# TouScruino-v3.net
KiCad netlist of a schematic drawn in EAGLE
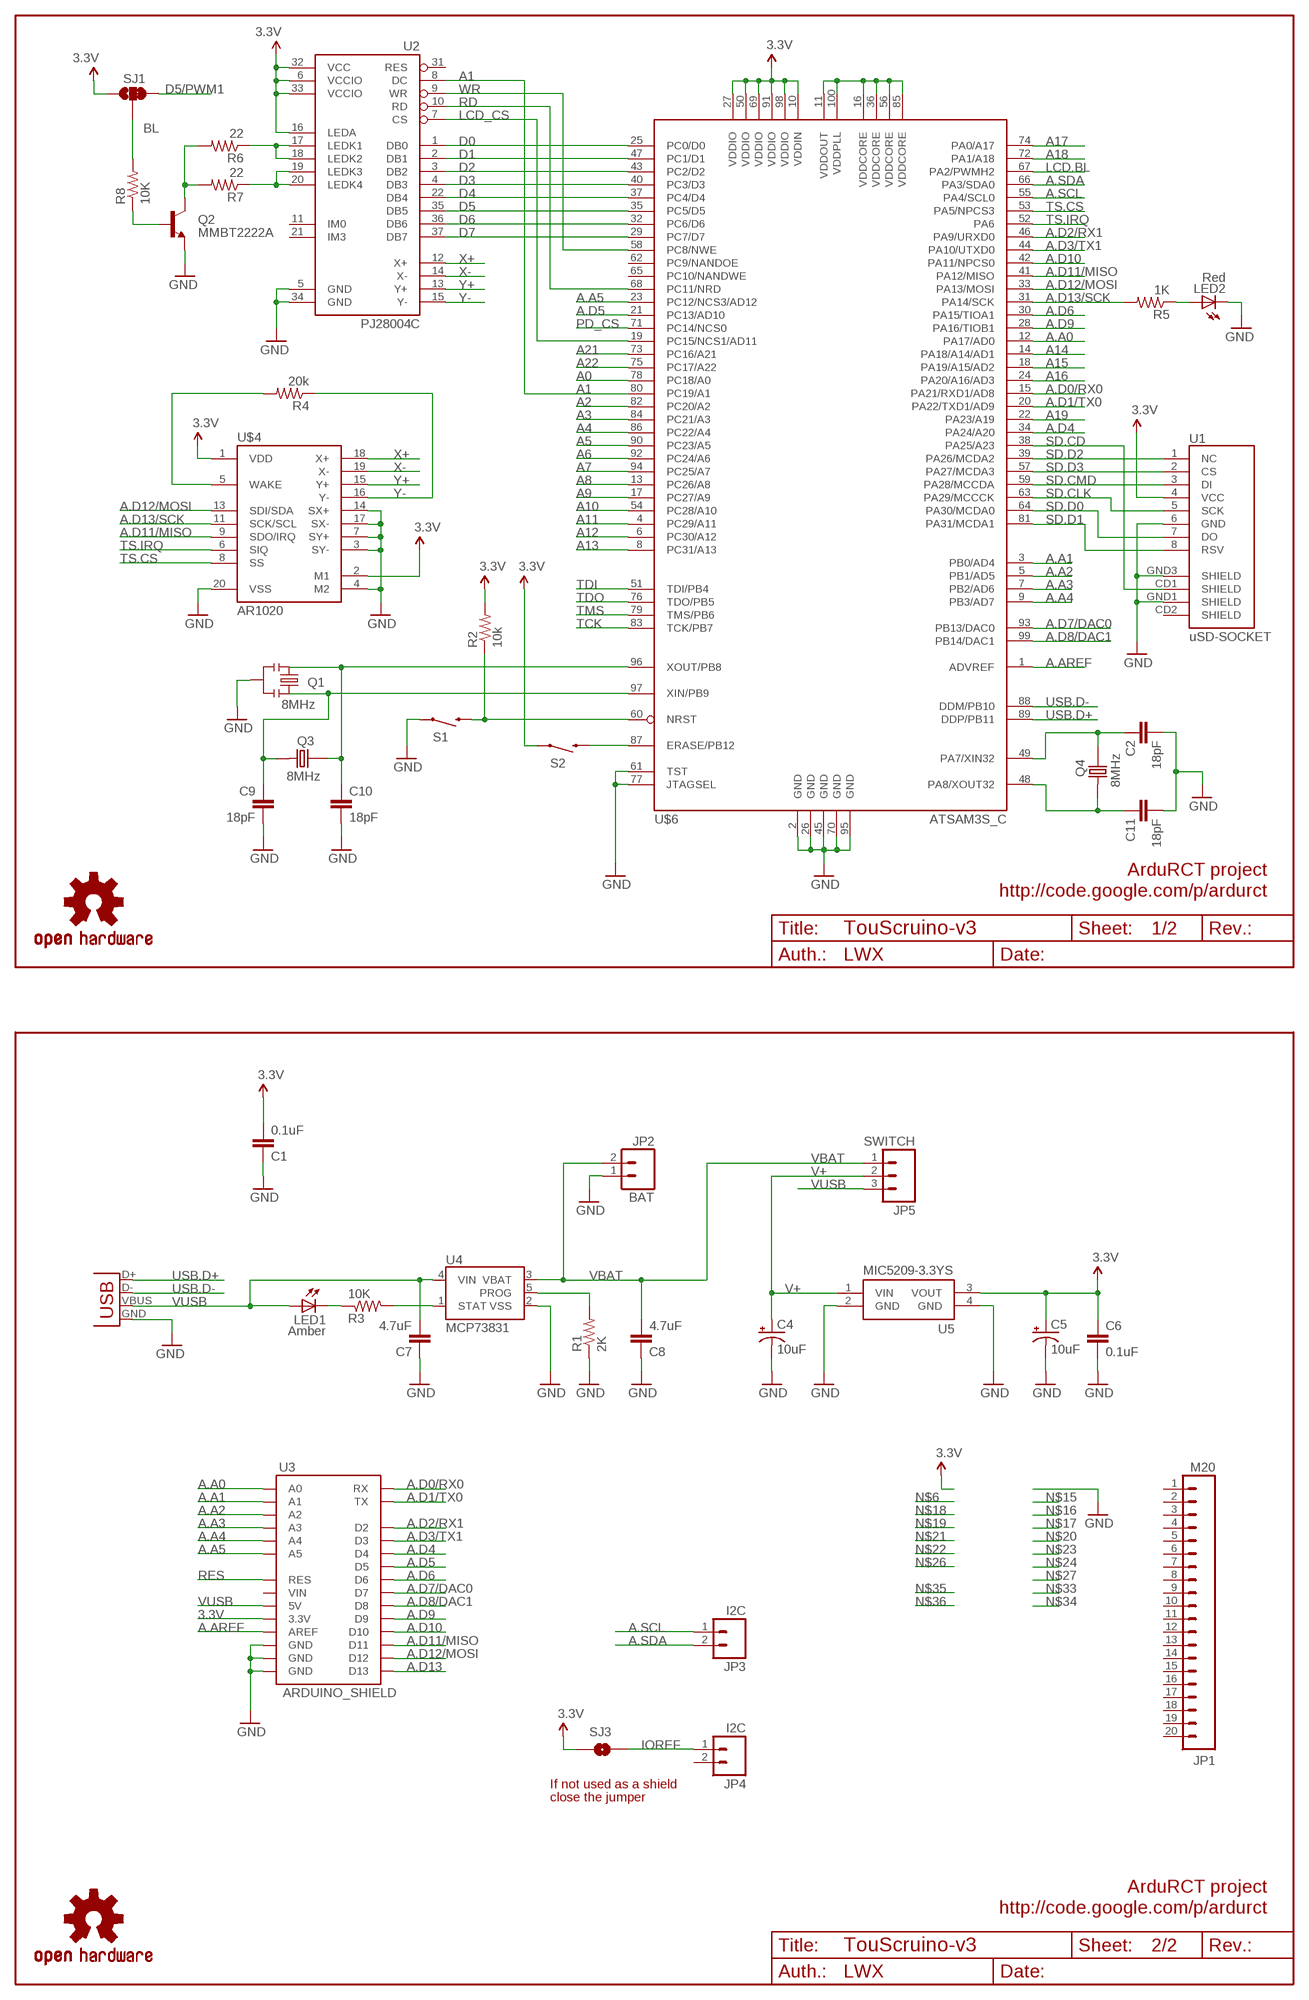
[diagram p0: schematic, sheet 1]

(export (version "E")
  (design (tool "Eeschema 10.0.6"))
  (components
    (comp (ref "C1")
      (value "0.1uF")
      (footprint "eagle-import:0805")
      (libsource (lib "eagle-import") (part "CAP0805"))
    )
    (comp (ref "C2")
      (value "18pF")
      (footprint "eagle-import:0603-CAP")
      (libsource (lib "eagle-import") (part "CAP0603-CAP"))
    )
    (comp (ref "C4")
      (value "10uF")
      (footprint "eagle-import:EIA3216")
      (libsource (lib "eagle-import") (part "CAP_POL1206"))
    )
    (comp (ref "C5")
      (value "10uF")
      (footprint "eagle-import:EIA3216")
      (libsource (lib "eagle-import") (part "CAP_POL1206"))
    )
    (comp (ref "C6")
      (value "0.1uF")
      (footprint "eagle-import:0805")
      (libsource (lib "eagle-import") (part "CAP0805"))
    )
    (comp (ref "C7")
      (value "4.7uF")
      (footprint "eagle-import:0805")
      (libsource (lib "eagle-import") (part "CAP0805"))
    )
    (comp (ref "C8")
      (value "4.7uF")
      (footprint "eagle-import:0805")
      (libsource (lib "eagle-import") (part "CAP0805"))
    )
    (comp (ref "C9")
      (value "18pF")
      (footprint "eagle-import:0603-CAP")
      (libsource (lib "eagle-import") (part "CAP0603-CAP"))
    )
    (comp (ref "C10")
      (value "18pF")
      (footprint "eagle-import:0603-CAP")
      (libsource (lib "eagle-import") (part "CAP0603-CAP"))
    )
    (comp (ref "C11")
      (value "18pF")
      (footprint "eagle-import:0603-CAP")
      (libsource (lib "eagle-import") (part "CAP0603-CAP"))
    )
    (comp (ref "JP1")
      (value "M20")
      (footprint "eagle-import:1X20")
      (libsource (lib "eagle-import") (part "M20"))
    )
    (comp (ref "JP2")
      (value "BAT")
      (footprint "eagle-import:JST-2-SMD")
      (libsource (lib "eagle-import") (part "M02-JST-2MM-SMT"))
    )
    (comp (ref "JP3")
      (value "I2C")
      (footprint "eagle-import:1X02")
      (libsource (lib "eagle-import") (part "M02"))
    )
    (comp (ref "JP4")
      (value "I2C")
      (footprint "eagle-import:1X02")
      (libsource (lib "eagle-import") (part "M02"))
    )
    (comp (ref "JP5")
      (value "SWITCH")
      (footprint "eagle-import:1X3_LONGPAD")
      (libsource (lib "eagle-import") (part "M03"))
    )
    (comp (ref "LED1")
      (value "Amber")
      (footprint "eagle-import:LED")
      (libsource (lib "eagle-import") (part "LED"))
    )
    (comp (ref "LED2")
      (value "Red")
      (footprint "eagle-import:LED-0805")
      (libsource (lib "eagle-import") (part "LED805"))
    )
    (comp (ref "Q1")
      (value "8MHz")
      (footprint "eagle-import:RESONATOR-SMD")
      (libsource (lib "eagle-import") (part "RESONATORSMD"))
    )
    (comp (ref "Q2")
      (value "MMBT2222A")
      (footprint "eagle-import:SOT23-3")
      (libsource (lib "eagle-import") (part "TRANSISTOR_NPNSOT23-3"))
    )
    (comp (ref "Q3")
      (value "8MHz")
      (footprint "eagle-import:CRYSTAL_5X3.2")
      (libsource (lib "eagle-import") (part "CRYSTAL_5X3.2"))
    )
    (comp (ref "Q4")
      (value "8MHz")
      (footprint "eagle-import:CRYSTAL_5X3.2")
      (libsource (lib "eagle-import") (part "CRYSTAL_5X3.2"))
    )
    (comp (ref "R1")
      (value "2K")
      (footprint "eagle-import:0805")
      (libsource (lib "eagle-import") (part "RESISTOR0805-RES"))
    )
    (comp (ref "R2")
      (value "10k")
      (footprint "eagle-import:0805")
      (libsource (lib "eagle-import") (part "RESISTOR0805-RES"))
    )
    (comp (ref "R3")
      (value "10K")
      (footprint "eagle-import:0805")
      (libsource (lib "eagle-import") (part "RESISTOR0805-RES"))
    )
    (comp (ref "R4")
      (value "20k")
      (footprint "eagle-import:0805")
      (libsource (lib "eagle-import") (part "RESISTOR0805-RES"))
    )
    (comp (ref "R5")
      (value "1K")
      (footprint "eagle-import:0805")
      (libsource (lib "eagle-import") (part "RESISTOR0805-RES"))
    )
    (comp (ref "R6")
      (value "22")
      (footprint "eagle-import:0805")
      (libsource (lib "eagle-import") (part "RESISTOR0805-RES"))
    )
    (comp (ref "R7")
      (value "22")
      (footprint "eagle-import:0805")
      (libsource (lib "eagle-import") (part "RESISTOR0805-RES"))
    )
    (comp (ref "R8")
      (value "10K")
      (footprint "eagle-import:0805")
      (libsource (lib "eagle-import") (part "RESISTOR0805-RES"))
    )
    (comp (ref "S1")
      (value "SWITCH-MOMENTARY-2SMD")
      (footprint "eagle-import:TACTILE_SWITCH_SMD")
      (libsource (lib "eagle-import") (part "SWITCH-MOMENTARY-2SMD"))
    )
    (comp (ref "S2")
      (value "SWITCH-MOMENTARY-2SMD")
      (footprint "eagle-import:TACTILE_SWITCH_SMD")
      (libsource (lib "eagle-import") (part "SWITCH-MOMENTARY-2SMD"))
    )
    (comp (ref "SJ1")
      (value "SJ_2WAYS_1-2")
      (footprint "eagle-import:SJ_2WAYS_1-2_S")
      (libsource (lib "eagle-import") (part "SJ_2WAYS_1-2"))
    )
    (comp (ref "SJ3")
      (value "SOLDERJUMPERNO")
      (footprint "eagle-import:SJ_2S-NO")
      (libsource (lib "eagle-import") (part "SOLDERJUMPERNO"))
    )
    (comp (ref "U$3")
      (value "OSHW-LOGOM")
      (footprint "eagle-import:OSHW-LOGO-M")
      (libsource (lib "eagle-import") (part "OSHW-LOGOM"))
    )
    (comp (ref "U$4")
      (value "AR1020")
      (footprint "eagle-import:SSOP20")
      (libsource (lib "eagle-import") (part "AR1020"))
    )
    (comp (ref "U$5")
      (value "OSHW-LOGOM")
      (footprint "eagle-import:OSHW-LOGO-M")
      (libsource (lib "eagle-import") (part "OSHW-LOGOM"))
    )
    (comp (ref "U$6")
      (value "ATSAM3S_C")
      (footprint "eagle-import:TQFP100")
      (libsource (lib "eagle-import") (part "ATSAM3S_C"))
    )
    (comp (ref "U1")
      (value "uSD-SOCKET")
      (footprint "eagle-import:MICRO-SD-SOCKET-PP")
      (libsource (lib "eagle-import") (part "USD-SOCKETNEW"))
    )
    (comp (ref "U2")
      (value "PJ28004C")
      (footprint "eagle-import:PJ28004C")
      (libsource (lib "eagle-import") (part "PJ28004C"))
    )
    (comp (ref "U3")
      (value "ARDUINO_SHIELD")
      (footprint "eagle-import:ARDUINO_SHIELD")
      (libsource (lib "eagle-import") (part "ARDUINO_SHIELD"))
    )
    (comp (ref "U4")
      (value "MCP73831")
      (footprint "eagle-import:SOT23-5")
      (libsource (lib "eagle-import") (part "MCP73831"))
    )
    (comp (ref "U5")
      (value "MIC5209-3.3YS")
      (footprint "eagle-import:SOT223")
      (libsource (lib "eagle-import") (part "MIC5209"))
    )
    (comp (ref "X1")
      (value "USBSMD")
      (footprint "eagle-import:USB-MINIB")
      (libsource (lib "eagle-import") (part "USBSMD"))
    )
  )
  (nets
    (net (code "1") (name "/A.A0") (class "Default")
      (node (ref "U$6") (pin "12") (pinfunction "PA17/AD0_12") (pintype "bidirectional"))
      (node (ref "U3") (pin "A0") (pinfunction "A0_A0") (pintype "bidirectional"))
    )
    (net (code "2") (name "/A.A1") (class "Default")
      (node (ref "U$6") (pin "3") (pinfunction "PB0/AD4_3") (pintype "bidirectional"))
      (node (ref "U3") (pin "A1") (pinfunction "A1_A1") (pintype "bidirectional"))
    )
    (net (code "3") (name "/A.A2") (class "Default")
      (node (ref "U$6") (pin "5") (pinfunction "PB1/AD5_5") (pintype "bidirectional"))
      (node (ref "U3") (pin "A2") (pinfunction "A2_A2") (pintype "bidirectional"))
    )
    (net (code "4") (name "/A.A3") (class "Default")
      (node (ref "U$6") (pin "7") (pinfunction "PB2/AD6_7") (pintype "bidirectional"))
      (node (ref "U3") (pin "A3") (pinfunction "A3_A3") (pintype "bidirectional"))
    )
    (net (code "5") (name "/A.A4") (class "Default")
      (node (ref "U$6") (pin "9") (pinfunction "PB3/AD7_9") (pintype "bidirectional"))
      (node (ref "U3") (pin "A4") (pinfunction "A4_A4") (pintype "bidirectional"))
    )
    (net (code "6") (name "/A.A5") (class "Default")
      (node (ref "U$6") (pin "23") (pinfunction "PC12/NCS3/AD12_23") (pintype "bidirectional"))
      (node (ref "U3") (pin "A5") (pinfunction "A5_A5") (pintype "bidirectional"))
    )
    (net (code "7") (name "/A.AREF") (class "Default")
      (node (ref "U$6") (pin "1") (pinfunction "ADVREF_1") (pintype "bidirectional"))
      (node (ref "U3") (pin "AREF") (pinfunction "AREF_AREF") (pintype "bidirectional"))
    )
    (net (code "8") (name "/A.D0{slash}RX0") (class "Default")
      (node (ref "U$6") (pin "15") (pinfunction "PA21/RXD1/AD8_15") (pintype "bidirectional"))
      (node (ref "U3") (pin "RX") (pinfunction "RX_RX") (pintype "bidirectional"))
    )
    (net (code "9") (name "/A.D1{slash}TX0") (class "Default")
      (node (ref "U$6") (pin "20") (pinfunction "PA22/TXD1/AD9_20") (pintype "bidirectional"))
      (node (ref "U3") (pin "TX") (pinfunction "TX_TX") (pintype "bidirectional"))
    )
    (net (code "10") (name "/A.D2{slash}RX1") (class "Default")
      (node (ref "U$6") (pin "46") (pinfunction "PA9/URXD0_46") (pintype "bidirectional"))
      (node (ref "U3") (pin "D2") (pinfunction "D2_D2") (pintype "bidirectional"))
    )
    (net (code "11") (name "/A.D3{slash}TX1") (class "Default")
      (node (ref "U$6") (pin "44") (pinfunction "PA10/UTXD0_44") (pintype "bidirectional"))
      (node (ref "U3") (pin "D3") (pinfunction "D3_D3") (pintype "bidirectional"))
    )
    (net (code "12") (name "/A.D4") (class "Default")
      (node (ref "U$6") (pin "34") (pinfunction "PA24/A20_34") (pintype "bidirectional"))
      (node (ref "U3") (pin "D4") (pinfunction "D4_D4") (pintype "bidirectional"))
    )
    (net (code "13") (name "/A.D5") (class "Default")
      (node (ref "U$6") (pin "21") (pinfunction "PC13/AD10_21") (pintype "bidirectional"))
      (node (ref "U3") (pin "D5") (pinfunction "D5_D5") (pintype "bidirectional"))
    )
    (net (code "14") (name "/A.D6") (class "Default")
      (node (ref "U$6") (pin "30") (pinfunction "PA15/TIOA1_30") (pintype "bidirectional"))
      (node (ref "U3") (pin "D6") (pinfunction "D6_D6") (pintype "bidirectional"))
    )
    (net (code "15") (name "/A.D7{slash}DAC0") (class "Default")
      (node (ref "U$6") (pin "93") (pinfunction "PB13/DAC0_93") (pintype "bidirectional"))
      (node (ref "U3") (pin "D7") (pinfunction "D7_D7") (pintype "bidirectional"))
    )
    (net (code "16") (name "/A.D8{slash}DAC1") (class "Default")
      (node (ref "U$6") (pin "99") (pinfunction "PB14/DAC1_99") (pintype "bidirectional"))
      (node (ref "U3") (pin "D8") (pinfunction "D8_D8") (pintype "bidirectional"))
    )
    (net (code "17") (name "/A.D9") (class "Default")
      (node (ref "U$6") (pin "28") (pinfunction "PA16/TIOB1_28") (pintype "bidirectional"))
      (node (ref "U3") (pin "D9") (pinfunction "D9_D9") (pintype "bidirectional"))
    )
    (net (code "18") (name "/A.D10") (class "Default")
      (node (ref "U$6") (pin "42") (pinfunction "PA11/NPCS0_42") (pintype "bidirectional"))
      (node (ref "U3") (pin "D10") (pinfunction "D10_D10") (pintype "bidirectional"))
    )
    (net (code "19") (name "/A.D11{slash}MISO") (class "Default")
      (node (ref "U$4") (pin "9") (pinfunction "SDO/IRQ_9") (pintype "bidirectional"))
      (node (ref "U$6") (pin "41") (pinfunction "PA12/MISO_41") (pintype "bidirectional"))
      (node (ref "U3") (pin "D11") (pinfunction "D11_D11") (pintype "bidirectional"))
    )
    (net (code "20") (name "/A.D12{slash}MOSI") (class "Default")
      (node (ref "U$4") (pin "13") (pinfunction "SDI/SDA_13") (pintype "bidirectional"))
      (node (ref "U$6") (pin "33") (pinfunction "PA13/MOSI_33") (pintype "bidirectional"))
      (node (ref "U3") (pin "D12") (pinfunction "D12_D12") (pintype "bidirectional"))
    )
    (net (code "21") (name "/A.D13") (class "Default")
      (node (ref "U3") (pin "D13") (pinfunction "D13_D13") (pintype "bidirectional"))
    )
    (net (code "22") (name "/A.D13{slash}SCK") (class "Default")
      (node (ref "R5") (pin "2") (pinfunction "2_2") (pintype "passive"))
      (node (ref "U$4") (pin "11") (pinfunction "SCK/SCL_11") (pintype "bidirectional"))
      (node (ref "U$6") (pin "31") (pinfunction "PA14/SCK_31") (pintype "bidirectional"))
    )
    (net (code "23") (name "/A.SCL") (class "Default")
      (node (ref "JP3") (pin "1") (pinfunction "1_1") (pintype "passive"))
      (node (ref "U$6") (pin "55") (pinfunction "PA4/SCL0_55") (pintype "bidirectional"))
    )
    (net (code "24") (name "/A.SDA") (class "Default")
      (node (ref "JP3") (pin "2") (pinfunction "2_2") (pintype "passive"))
      (node (ref "U$6") (pin "66") (pinfunction "PA3/SDA0_66") (pintype "bidirectional"))
    )
    (net (code "25") (name "/A0") (class "Default")
      (node (ref "U$6") (pin "78") (pinfunction "PC18/A0_78") (pintype "bidirectional"))
    )
    (net (code "26") (name "/A1") (class "Default")
      (node (ref "U$6") (pin "80") (pinfunction "PC19/A1_80") (pintype "bidirectional"))
      (node (ref "U2") (pin "8") (pinfunction "DC_8") (pintype "bidirectional"))
    )
    (net (code "27") (name "/A2") (class "Default")
      (node (ref "U$6") (pin "82") (pinfunction "PC20/A2_82") (pintype "bidirectional"))
    )
    (net (code "28") (name "/A3") (class "Default")
      (node (ref "U$6") (pin "84") (pinfunction "PC21/A3_84") (pintype "bidirectional"))
    )
    (net (code "29") (name "/A4") (class "Default")
      (node (ref "U$6") (pin "86") (pinfunction "PC22/A4_86") (pintype "bidirectional"))
    )
    (net (code "30") (name "/A5") (class "Default")
      (node (ref "U$6") (pin "90") (pinfunction "PC23/A5_90") (pintype "bidirectional"))
    )
    (net (code "31") (name "/A6") (class "Default")
      (node (ref "U$6") (pin "92") (pinfunction "PC24/A6_92") (pintype "bidirectional"))
    )
    (net (code "32") (name "/A7") (class "Default")
      (node (ref "U$6") (pin "94") (pinfunction "PC25/A7_94") (pintype "bidirectional"))
    )
    (net (code "33") (name "/A8") (class "Default")
      (node (ref "U$6") (pin "13") (pinfunction "PC26/A8_13") (pintype "bidirectional"))
    )
    (net (code "34") (name "/A9") (class "Default")
      (node (ref "U$6") (pin "17") (pinfunction "PC27/A9_17") (pintype "bidirectional"))
    )
    (net (code "35") (name "/A10") (class "Default")
      (node (ref "U$6") (pin "54") (pinfunction "PC28/A10_54") (pintype "bidirectional"))
    )
    (net (code "36") (name "/A11") (class "Default")
      (node (ref "U$6") (pin "4") (pinfunction "PC29/A11_4") (pintype "bidirectional"))
    )
    (net (code "37") (name "/A12") (class "Default")
      (node (ref "U$6") (pin "6") (pinfunction "PC30/A12_6") (pintype "bidirectional"))
    )
    (net (code "38") (name "/A13") (class "Default")
      (node (ref "U$6") (pin "8") (pinfunction "PC31/A13_8") (pintype "bidirectional"))
    )
    (net (code "39") (name "/A14") (class "Default")
      (node (ref "U$6") (pin "14") (pinfunction "PA18/A14/AD1_14") (pintype "bidirectional"))
    )
    (net (code "40") (name "/A15") (class "Default")
      (node (ref "U$6") (pin "18") (pinfunction "PA19/A15/AD2_18") (pintype "bidirectional"))
    )
    (net (code "41") (name "/A16") (class "Default")
      (node (ref "U$6") (pin "24") (pinfunction "PA20/A16/AD3_24") (pintype "bidirectional"))
    )
    (net (code "42") (name "/A17") (class "Default")
      (node (ref "U$6") (pin "74") (pinfunction "PA0/A17_74") (pintype "bidirectional"))
    )
    (net (code "43") (name "/A18") (class "Default")
      (node (ref "U$6") (pin "72") (pinfunction "PA1/A18_72") (pintype "bidirectional"))
    )
    (net (code "44") (name "/A19") (class "Default")
      (node (ref "U$6") (pin "22") (pinfunction "PA23/A19_22") (pintype "bidirectional"))
    )
    (net (code "45") (name "/A21") (class "Default")
      (node (ref "U$6") (pin "73") (pinfunction "PC16/A21_73") (pintype "bidirectional"))
    )
    (net (code "46") (name "/A22") (class "Default")
      (node (ref "U$6") (pin "75") (pinfunction "PC17/A22_75") (pintype "bidirectional"))
    )
    (net (code "47") (name "/BL") (class "Default")
      (node (ref "R8") (pin "2") (pinfunction "2_2") (pintype "passive"))
      (node (ref "SJ1") (pin "2") (pinfunction "2_2") (pintype "passive"))
    )
    (net (code "48") (name "/D0") (class "Default")
      (node (ref "U$6") (pin "25") (pinfunction "PC0/D0_25") (pintype "bidirectional"))
      (node (ref "U2") (pin "1") (pinfunction "DB0_1") (pintype "bidirectional"))
    )
    (net (code "49") (name "/D1") (class "Default")
      (node (ref "U$6") (pin "47") (pinfunction "PC1/D1_47") (pintype "bidirectional"))
      (node (ref "U2") (pin "2") (pinfunction "DB1_2") (pintype "bidirectional"))
    )
    (net (code "50") (name "/D2") (class "Default")
      (node (ref "U$6") (pin "43") (pinfunction "PC2/D2_43") (pintype "bidirectional"))
      (node (ref "U2") (pin "3") (pinfunction "DB2_3") (pintype "bidirectional"))
    )
    (net (code "51") (name "/D3") (class "Default")
      (node (ref "U$6") (pin "40") (pinfunction "PC3/D3_40") (pintype "bidirectional"))
      (node (ref "U2") (pin "4") (pinfunction "DB3_4") (pintype "bidirectional"))
    )
    (net (code "52") (name "/D4") (class "Default")
      (node (ref "U$6") (pin "37") (pinfunction "PC4/D4_37") (pintype "bidirectional"))
      (node (ref "U2") (pin "22") (pinfunction "DB4_22") (pintype "bidirectional"))
    )
    (net (code "53") (name "/D5") (class "Default")
      (node (ref "U$6") (pin "35") (pinfunction "PC5/D5_35") (pintype "bidirectional"))
      (node (ref "U2") (pin "35") (pinfunction "DB5_35") (pintype "bidirectional"))
    )
    (net (code "54") (name "/D5{slash}PWM1") (class "Default")
      (node (ref "SJ1") (pin "1") (pinfunction "1_1") (pintype "passive"))
    )
    (net (code "55") (name "/D6") (class "Default")
      (node (ref "U$6") (pin "32") (pinfunction "PC6/D6_32") (pintype "bidirectional"))
      (node (ref "U2") (pin "36") (pinfunction "DB6_36") (pintype "bidirectional"))
    )
    (net (code "56") (name "/D7") (class "Default")
      (node (ref "U$6") (pin "29") (pinfunction "PC7/D7_29") (pintype "bidirectional"))
      (node (ref "U2") (pin "37") (pinfunction "DB7_37") (pintype "bidirectional"))
    )
    (net (code "57") (name "/IOREF") (class "Default")
      (node (ref "JP4") (pin "1") (pinfunction "1_1") (pintype "passive"))
      (node (ref "SJ3") (pin "2") (pinfunction "2_2") (pintype "passive"))
    )
    (net (code "58") (name "/LCD.BL") (class "Default")
      (node (ref "U$6") (pin "67") (pinfunction "PA2/PWMH2_67") (pintype "bidirectional"))
    )
    (net (code "59") (name "/LCD_CS") (class "Default")
      (node (ref "U$6") (pin "19") (pinfunction "PC15/NCS1/AD11_19") (pintype "bidirectional"))
      (node (ref "U2") (pin "7") (pinfunction "CS_7") (pintype "bidirectional"))
    )
    (net (code "77") (name "/PD_CS") (class "Default")
      (node (ref "U$6") (pin "71") (pinfunction "PC14/NCS0_71") (pintype "bidirectional"))
    )
    (net (code "78") (name "/RD") (class "Default")
      (node (ref "U$6") (pin "68") (pinfunction "PC11/NRD_68") (pintype "bidirectional"))
      (node (ref "U2") (pin "10") (pinfunction "RD_10") (pintype "bidirectional"))
    )
    (net (code "79") (name "/RES") (class "Default")
      (node (ref "U3") (pin "RES") (pinfunction "RES_RES") (pintype "bidirectional"))
    )
    (net (code "80") (name "/SD.CD") (class "Default")
      (node (ref "U$6") (pin "38") (pinfunction "PA25/A23_38") (pintype "bidirectional"))
      (node (ref "U1") (pin "CD1") (pinfunction "SHIELD_CD1") (pintype "bidirectional"))
    )
    (net (code "81") (name "/SD.CLK") (class "Default")
      (node (ref "U$6") (pin "63") (pinfunction "PA29/MCCCK_63") (pintype "bidirectional"))
      (node (ref "U1") (pin "5") (pinfunction "SCK_5") (pintype "bidirectional"))
    )
    (net (code "82") (name "/SD.CMD") (class "Default")
      (node (ref "U$6") (pin "59") (pinfunction "PA28/MCCDA_59") (pintype "bidirectional"))
      (node (ref "U1") (pin "3") (pinfunction "DI_3") (pintype "bidirectional"))
    )
    (net (code "83") (name "/SD.D0") (class "Default")
      (node (ref "U$6") (pin "64") (pinfunction "PA30/MCDA0_64") (pintype "bidirectional"))
      (node (ref "U1") (pin "7") (pinfunction "DO_7") (pintype "bidirectional"))
    )
    (net (code "84") (name "/SD.D1") (class "Default")
      (node (ref "U$6") (pin "81") (pinfunction "PA31/MCDA1_81") (pintype "bidirectional"))
      (node (ref "U1") (pin "8") (pinfunction "RSV_8") (pintype "bidirectional"))
    )
    (net (code "85") (name "/SD.D2") (class "Default")
      (node (ref "U$6") (pin "39") (pinfunction "PA26/MCDA2_39") (pintype "bidirectional"))
      (node (ref "U1") (pin "1") (pinfunction "NC_1") (pintype "bidirectional"))
    )
    (net (code "86") (name "/SD.D3") (class "Default")
      (node (ref "U$6") (pin "57") (pinfunction "PA27/MCDA3_57") (pintype "bidirectional"))
      (node (ref "U1") (pin "2") (pinfunction "CS_2") (pintype "bidirectional"))
    )
    (net (code "87") (name "/TCK") (class "Default")
      (node (ref "U$6") (pin "83") (pinfunction "TCK/PB7_83") (pintype "bidirectional"))
    )
    (net (code "88") (name "/TDI") (class "Default")
      (node (ref "U$6") (pin "51") (pinfunction "TDI/PB4_51") (pintype "bidirectional"))
    )
    (net (code "89") (name "/TDO") (class "Default")
      (node (ref "U$6") (pin "76") (pinfunction "TDO/PB5_76") (pintype "bidirectional"))
    )
    (net (code "90") (name "/TMS") (class "Default")
      (node (ref "U$6") (pin "79") (pinfunction "TMS/PB6_79") (pintype "bidirectional"))
    )
    (net (code "91") (name "/TS.CS") (class "Default")
      (node (ref "U$4") (pin "8") (pinfunction "SS_8") (pintype "bidirectional"))
      (node (ref "U$6") (pin "53") (pinfunction "PA5/NPCS3_53") (pintype "bidirectional"))
    )
    (net (code "92") (name "/TS.IRQ") (class "Default")
      (node (ref "U$4") (pin "6") (pinfunction "SIQ_6") (pintype "bidirectional"))
      (node (ref "U$6") (pin "52") (pinfunction "PA6_52") (pintype "bidirectional"))
    )
    (net (code "93") (name "/USB.D+") (class "Default")
      (node (ref "U$6") (pin "89") (pinfunction "DDP/PB11_89") (pintype "bidirectional"))
      (node (ref "X1") (pin "D+") (pinfunction "D+_D+") (pintype "bidirectional"))
    )
    (net (code "94") (name "/USB.D-") (class "Default")
      (node (ref "U$6") (pin "88") (pinfunction "DDM/PB10_88") (pintype "bidirectional"))
      (node (ref "X1") (pin "D-") (pinfunction "D-_D-") (pintype "bidirectional"))
    )
    (net (code "95") (name "/V+") (class "Default")
      (node (ref "C4") (pin "A") (pinfunction "+_A") (pintype "passive"))
      (node (ref "JP5") (pin "2") (pinfunction "2_2") (pintype "passive"))
      (node (ref "U5") (pin "1") (pinfunction "VIN_1") (pintype "bidirectional"))
    )
    (net (code "96") (name "/VBAT") (class "Default")
      (node (ref "C8") (pin "2") (pinfunction "2_2") (pintype "passive"))
      (node (ref "JP2") (pin "2") (pinfunction "2_2") (pintype "passive"))
      (node (ref "JP5") (pin "1") (pinfunction "1_1") (pintype "passive"))
      (node (ref "U4") (pin "3") (pinfunction "VBAT_3") (pintype "power_in"))
    )
    (net (code "97") (name "/VUSB") (class "Default")
      (node (ref "C7") (pin "2") (pinfunction "2_2") (pintype "passive"))
      (node (ref "JP5") (pin "3") (pinfunction "3_3") (pintype "passive"))
      (node (ref "LED1") (pin "A1") (pinfunction "A_A1") (pintype "passive"))
      (node (ref "U3") (pin "5V") (pinfunction "5V_5V") (pintype "bidirectional"))
      (node (ref "U4") (pin "4") (pinfunction "VIN_4") (pintype "power_in"))
      (node (ref "X1") (pin "VBUS") (pinfunction "VBUS_VBUS") (pintype "bidirectional"))
    )
    (net (code "98") (name "/WR") (class "Default")
      (node (ref "U$6") (pin "58") (pinfunction "PC8/NWE_58") (pintype "bidirectional"))
      (node (ref "U2") (pin "9") (pinfunction "WR_9") (pintype "bidirectional"))
    )
    (net (code "99") (name "/X+") (class "Default")
      (node (ref "U$4") (pin "18") (pinfunction "X+_18") (pintype "bidirectional"))
      (node (ref "U2") (pin "12") (pinfunction "X+_12") (pintype "bidirectional"))
    )
    (net (code "100") (name "/X-") (class "Default")
      (node (ref "U$4") (pin "19") (pinfunction "X-_19") (pintype "bidirectional"))
      (node (ref "U2") (pin "14") (pinfunction "X-_14") (pintype "bidirectional"))
    )
    (net (code "101") (name "/Y+") (class "Default")
      (node (ref "U$4") (pin "15") (pinfunction "Y+_15") (pintype "bidirectional"))
      (node (ref "U2") (pin "13") (pinfunction "Y+_13") (pintype "bidirectional"))
    )
    (net (code "102") (name "/Y-") (class "Default")
      (node (ref "R4") (pin "1") (pinfunction "1_1") (pintype "passive"))
      (node (ref "U$4") (pin "16") (pinfunction "Y-_16") (pintype "bidirectional"))
      (node (ref "U2") (pin "15") (pinfunction "Y-_15") (pintype "bidirectional"))
    )
    (net (code "103") (name "3.3V") (class "Default")
      (node (ref "C1") (pin "2") (pinfunction "2_2") (pintype "passive"))
      (node (ref "C5") (pin "A") (pinfunction "+_A") (pintype "passive"))
      (node (ref "C6") (pin "1") (pinfunction "1_1") (pintype "passive"))
      (node (ref "R2") (pin "2") (pinfunction "2_2") (pintype "passive"))
      (node (ref "S2") (pin "1") (pinfunction "1_1") (pintype "passive"))
      (node (ref "SJ1") (pin "3") (pinfunction "3_3") (pintype "passive"))
      (node (ref "SJ3") (pin "1") (pinfunction "1_1") (pintype "passive"))
      (node (ref "U$4") (pin "1") (pinfunction "VDD_1") (pintype "bidirectional"))
      (node (ref "U$4") (pin "2") (pinfunction "M1_2") (pintype "bidirectional"))
      (node (ref "U$6") (pin "10") (pinfunction "VDDIN_10") (pintype "bidirectional"))
      (node (ref "U$6") (pin "27") (pinfunction "VDDIO_27") (pintype "bidirectional"))
      (node (ref "U$6") (pin "50") (pinfunction "VDDIO_50") (pintype "bidirectional"))
      (node (ref "U$6") (pin "69") (pinfunction "VDDIO_69") (pintype "bidirectional"))
      (node (ref "U$6") (pin "91") (pinfunction "VDDIO_91") (pintype "bidirectional"))
      (node (ref "U$6") (pin "98") (pinfunction "VDDIO_98") (pintype "bidirectional"))
      (node (ref "U1") (pin "4") (pinfunction "VCC_4") (pintype "bidirectional"))
      (node (ref "U2") (pin "16") (pinfunction "LEDA_16") (pintype "bidirectional"))
      (node (ref "U2") (pin "32") (pinfunction "VCC_32") (pintype "bidirectional"))
      (node (ref "U2") (pin "33") (pinfunction "VCCIO_33") (pintype "bidirectional"))
      (node (ref "U2") (pin "6") (pinfunction "VCCIO_6") (pintype "bidirectional"))
      (node (ref "U3") (pin "3.3V") (pinfunction "3.3V_3.3V") (pintype "bidirectional"))
      (node (ref "U5") (pin "3") (pinfunction "VOUT_3") (pintype "bidirectional"))
    )
    (net (code "104") (name "GND") (class "Default")
      (node (ref "C1") (pin "1") (pinfunction "1_1") (pintype "passive"))
      (node (ref "C10") (pin "2") (pinfunction "2_2") (pintype "passive"))
      (node (ref "C11") (pin "2") (pinfunction "2_2") (pintype "passive"))
      (node (ref "C2") (pin "2") (pinfunction "2_2") (pintype "passive"))
      (node (ref "C4") (pin "C") (pinfunction "-_C") (pintype "passive"))
      (node (ref "C5") (pin "C") (pinfunction "-_C") (pintype "passive"))
      (node (ref "C6") (pin "2") (pinfunction "2_2") (pintype "passive"))
      (node (ref "C7") (pin "1") (pinfunction "1_1") (pintype "passive"))
      (node (ref "C8") (pin "1") (pinfunction "1_1") (pintype "passive"))
      (node (ref "C9") (pin "2") (pinfunction "2_2") (pintype "passive"))
      (node (ref "JP2") (pin "1") (pinfunction "1_1") (pintype "passive"))
      (node (ref "LED2") (pin "2") (pinfunction "C_2") (pintype "passive"))
      (node (ref "Q1") (pin "2") (pinfunction "2_2") (pintype "passive"))
      (node (ref "Q2") (pin "2") (pinfunction "E_2") (pintype "passive"))
      (node (ref "R1") (pin "1") (pinfunction "1_1") (pintype "passive"))
      (node (ref "S1") (pin "1") (pinfunction "1_1") (pintype "passive"))
      (node (ref "U$4") (pin "14") (pinfunction "SX+_14") (pintype "bidirectional"))
      (node (ref "U$4") (pin "17") (pinfunction "SX-_17") (pintype "bidirectional"))
      (node (ref "U$4") (pin "20") (pinfunction "VSS_20") (pintype "bidirectional"))
      (node (ref "U$4") (pin "3") (pinfunction "SY-_3") (pintype "bidirectional"))
      (node (ref "U$4") (pin "4") (pinfunction "M2_4") (pintype "bidirectional"))
      (node (ref "U$4") (pin "7") (pinfunction "SY+_7") (pintype "bidirectional"))
      (node (ref "U$6") (pin "2") (pinfunction "GND_2") (pintype "bidirectional"))
      (node (ref "U$6") (pin "26") (pinfunction "GND_26") (pintype "bidirectional"))
      (node (ref "U$6") (pin "45") (pinfunction "GND_45") (pintype "bidirectional"))
      (node (ref "U$6") (pin "61") (pinfunction "TST_61") (pintype "bidirectional"))
      (node (ref "U$6") (pin "70") (pinfunction "GND_70") (pintype "bidirectional"))
      (node (ref "U$6") (pin "77") (pinfunction "JTAGSEL_77") (pintype "bidirectional"))
      (node (ref "U$6") (pin "95") (pinfunction "GND_95") (pintype "bidirectional"))
      (node (ref "U1") (pin "6") (pinfunction "GND_6") (pintype "bidirectional"))
      (node (ref "U1") (pin "GND1") (pinfunction "SHIELD_GND1") (pintype "bidirectional"))
      (node (ref "U1") (pin "GND3") (pinfunction "SHIELD_GND3") (pintype "bidirectional"))
      (node (ref "U2") (pin "34") (pinfunction "GND_34") (pintype "bidirectional"))
      (node (ref "U2") (pin "5") (pinfunction "GND_5") (pintype "bidirectional"))
      (node (ref "U3") (pin "GND@0") (pinfunction "GND_GND@0") (pintype "bidirectional"))
      (node (ref "U3") (pin "GND@1") (pinfunction "GND_GND@1") (pintype "bidirectional"))
      (node (ref "U3") (pin "GND@2") (pinfunction "GND_GND@2") (pintype "bidirectional"))
      (node (ref "U4") (pin "2") (pinfunction "VSS_2") (pintype "power_in"))
      (node (ref "U5") (pin "2") (pinfunction "GND_2") (pintype "bidirectional"))
      (node (ref "U5") (pin "4") (pinfunction "GND_4") (pintype "bidirectional"))
      (node (ref "X1") (pin "GND") (pinfunction "GND_GND") (pintype "bidirectional"))
    )
    (net (code "105") (name "Net-(LED1-C)") (class "Default")
      (node (ref "LED1") (pin "C1") (pinfunction "C_C1") (pintype "passive"))
      (node (ref "R3") (pin "1") (pinfunction "1_1") (pintype "passive"))
    )
    (net (code "106") (name "Net-(LED2-A)") (class "Default")
      (node (ref "LED2") (pin "1") (pinfunction "A_1") (pintype "passive"))
      (node (ref "R5") (pin "1") (pinfunction "1_1") (pintype "passive"))
    )
    (net (code "107") (name "Net-(Q2-B)") (class "Default")
      (node (ref "Q2") (pin "1") (pinfunction "B_1") (pintype "passive"))
      (node (ref "R8") (pin "1") (pinfunction "1_1") (pintype "passive"))
    )
    (net (code "108") (name "Net-(Q2-C)") (class "Default")
      (node (ref "Q2") (pin "3") (pinfunction "C_3") (pintype "passive"))
      (node (ref "R6") (pin "2") (pinfunction "2_2") (pintype "passive"))
      (node (ref "R7") (pin "2") (pinfunction "2_2") (pintype "passive"))
    )
    (net (code "109") (name "Net-(S1-2)") (class "Default")
      (node (ref "R2") (pin "1") (pinfunction "1_1") (pintype "passive"))
      (node (ref "S1") (pin "3") (pinfunction "2_3") (pintype "passive"))
      (node (ref "U$6") (pin "60") (pinfunction "NRST_60") (pintype "bidirectional"))
    )
    (net (code "110") (name "Net-(S2-2)") (class "Default")
      (node (ref "S2") (pin "3") (pinfunction "2_3") (pintype "passive"))
      (node (ref "U$6") (pin "87") (pinfunction "ERASE/PB12_87") (pintype "bidirectional"))
    )
    (net (code "111") (name "Net-(U$4-WAKE)") (class "Default")
      (node (ref "R4") (pin "2") (pinfunction "2_2") (pintype "passive"))
      (node (ref "U$4") (pin "5") (pinfunction "WAKE_5") (pintype "bidirectional"))
    )
    (net (code "112") (name "Net-(U$6-PA7{slash}XIN32)") (class "Default")
      (node (ref "C2") (pin "1") (pinfunction "1_1") (pintype "passive"))
      (node (ref "Q4") (pin "1") (pinfunction "1_1") (pintype "passive"))
      (node (ref "U$6") (pin "49") (pinfunction "PA7/XIN32_49") (pintype "bidirectional"))
    )
    (net (code "113") (name "Net-(U$6-PA8{slash}XOUT32)") (class "Default")
      (node (ref "C11") (pin "1") (pinfunction "1_1") (pintype "passive"))
      (node (ref "Q4") (pin "2") (pinfunction "2_2") (pintype "passive"))
      (node (ref "U$6") (pin "48") (pinfunction "PA8/XOUT32_48") (pintype "bidirectional"))
    )
    (net (code "114") (name "Net-(U$6-VDDOUT)") (class "Default")
      (node (ref "U$6") (pin "100") (pinfunction "VDDPLL_100") (pintype "bidirectional"))
      (node (ref "U$6") (pin "11") (pinfunction "VDDOUT_11") (pintype "bidirectional"))
      (node (ref "U$6") (pin "16") (pinfunction "VDDCORE_16") (pintype "bidirectional"))
      (node (ref "U$6") (pin "36") (pinfunction "VDDCORE_36") (pintype "bidirectional"))
      (node (ref "U$6") (pin "56") (pinfunction "VDDCORE_56") (pintype "bidirectional"))
      (node (ref "U$6") (pin "85") (pinfunction "VDDCORE_85") (pintype "bidirectional"))
    )
    (net (code "115") (name "Net-(U$6-XIN{slash}PB9)") (class "Default")
      (node (ref "C9") (pin "1") (pinfunction "1_1") (pintype "passive"))
      (node (ref "Q1") (pin "1") (pinfunction "1_1") (pintype "passive"))
      (node (ref "Q3") (pin "2") (pinfunction "2_2") (pintype "passive"))
      (node (ref "U$6") (pin "97") (pinfunction "XIN/PB9_97") (pintype "bidirectional"))
    )
    (net (code "116") (name "Net-(U$6-XOUT{slash}PB8)") (class "Default")
      (node (ref "C10") (pin "1") (pinfunction "1_1") (pintype "passive"))
      (node (ref "Q1") (pin "3") (pinfunction "3_3") (pintype "passive"))
      (node (ref "Q3") (pin "1") (pinfunction "1_1") (pintype "passive"))
      (node (ref "U$6") (pin "96") (pinfunction "XOUT/PB8_96") (pintype "bidirectional"))
    )
    (net (code "117") (name "Net-(U2-LEDK1)") (class "Default")
      (node (ref "R6") (pin "1") (pinfunction "1_1") (pintype "passive"))
      (node (ref "U2") (pin "17") (pinfunction "LEDK1_17") (pintype "bidirectional"))
      (node (ref "U2") (pin "18") (pinfunction "LEDK2_18") (pintype "bidirectional"))
    )
    (net (code "118") (name "Net-(U2-LEDK3)") (class "Default")
      (node (ref "R7") (pin "1") (pinfunction "1_1") (pintype "passive"))
      (node (ref "U2") (pin "19") (pinfunction "LEDK3_19") (pintype "bidirectional"))
      (node (ref "U2") (pin "20") (pinfunction "LEDK4_20") (pintype "bidirectional"))
    )
    (net (code "119") (name "Net-(U4-PROG)") (class "Default")
      (node (ref "R1") (pin "2") (pinfunction "2_2") (pintype "passive"))
      (node (ref "U4") (pin "5") (pinfunction "PROG_5") (pintype "input"))
    )
    (net (code "120") (name "Net-(U4-STAT)") (class "Default")
      (node (ref "R3") (pin "2") (pinfunction "2_2") (pintype "passive"))
      (node (ref "U4") (pin "1") (pinfunction "STAT_1") (pintype "output"))
    )
    (net (code "121") (name "unconnected-(JP1-Pad1)") (class "Default")
      (node (ref "JP1") (pin "1") (pinfunction "1_1") (pintype "passive"))
    )
    (net (code "122") (name "unconnected-(JP1-Pad2)") (class "Default")
      (node (ref "JP1") (pin "2") (pinfunction "2_2") (pintype "passive"))
    )
    (net (code "123") (name "unconnected-(JP1-Pad3)") (class "Default")
      (node (ref "JP1") (pin "3") (pinfunction "3_3") (pintype "passive"))
    )
    (net (code "124") (name "unconnected-(JP1-Pad4)") (class "Default")
      (node (ref "JP1") (pin "4") (pinfunction "4_4") (pintype "passive"))
    )
    (net (code "125") (name "unconnected-(JP1-Pad5)") (class "Default")
      (node (ref "JP1") (pin "5") (pinfunction "5_5") (pintype "passive"))
    )
    (net (code "126") (name "unconnected-(JP1-Pad6)") (class "Default")
      (node (ref "JP1") (pin "6") (pinfunction "6_6") (pintype "passive"))
    )
    (net (code "127") (name "unconnected-(JP1-Pad7)") (class "Default")
      (node (ref "JP1") (pin "7") (pinfunction "7_7") (pintype "passive"))
    )
    (net (code "128") (name "unconnected-(JP1-Pad8)") (class "Default")
      (node (ref "JP1") (pin "8") (pinfunction "8_8") (pintype "passive"))
    )
    (net (code "129") (name "unconnected-(JP1-Pad9)") (class "Default")
      (node (ref "JP1") (pin "9") (pinfunction "9_9") (pintype "passive"))
    )
    (net (code "130") (name "unconnected-(JP1-Pad10)") (class "Default")
      (node (ref "JP1") (pin "10") (pinfunction "10_10") (pintype "passive"))
    )
    (net (code "131") (name "unconnected-(JP1-Pad11)") (class "Default")
      (node (ref "JP1") (pin "11") (pinfunction "11_11") (pintype "passive"))
    )
    (net (code "132") (name "unconnected-(JP1-Pad12)") (class "Default")
      (node (ref "JP1") (pin "12") (pinfunction "12_12") (pintype "passive"))
    )
    (net (code "133") (name "unconnected-(JP1-Pad13)") (class "Default")
      (node (ref "JP1") (pin "13") (pinfunction "13_13") (pintype "passive"))
    )
    (net (code "134") (name "unconnected-(JP1-Pad14)") (class "Default")
      (node (ref "JP1") (pin "14") (pinfunction "14_14") (pintype "passive"))
    )
    (net (code "135") (name "unconnected-(JP1-Pad15)") (class "Default")
      (node (ref "JP1") (pin "15") (pinfunction "15_15") (pintype "passive"))
    )
    (net (code "136") (name "unconnected-(JP1-Pad16)") (class "Default")
      (node (ref "JP1") (pin "16") (pinfunction "16_16") (pintype "passive"))
    )
    (net (code "137") (name "unconnected-(JP1-Pad17)") (class "Default")
      (node (ref "JP1") (pin "17") (pinfunction "17_17") (pintype "passive"))
    )
    (net (code "138") (name "unconnected-(JP1-Pad18)") (class "Default")
      (node (ref "JP1") (pin "18") (pinfunction "18_18") (pintype "passive"))
    )
    (net (code "139") (name "unconnected-(JP1-Pad19)") (class "Default")
      (node (ref "JP1") (pin "19") (pinfunction "19_19") (pintype "passive"))
    )
    (net (code "140") (name "unconnected-(JP1-Pad20)") (class "Default")
      (node (ref "JP1") (pin "20") (pinfunction "20_20") (pintype "passive"))
    )
    (net (code "141") (name "unconnected-(JP4-Pad2)") (class "Default")
      (node (ref "JP4") (pin "2") (pinfunction "2_2") (pintype "passive"))
    )
    (net (code "142") (name "unconnected-(U$6-PC9{slash}NANDOE-Pad62)") (class "Default")
      (node (ref "U$6") (pin "62") (pinfunction "PC9/NANDOE_62") (pintype "bidirectional"))
    )
    (net (code "143") (name "unconnected-(U$6-PC10{slash}NANDWE-Pad65)") (class "Default")
      (node (ref "U$6") (pin "65") (pinfunction "PC10/NANDWE_65") (pintype "bidirectional"))
    )
    (net (code "144") (name "unconnected-(U1-SHIELD-PadCD2)") (class "Default")
      (node (ref "U1") (pin "CD2") (pinfunction "SHIELD_CD2") (pintype "bidirectional"))
    )
    (net (code "145") (name "unconnected-(U2-IM0-Pad11)") (class "Default")
      (node (ref "U2") (pin "11") (pinfunction "IM0_11") (pintype "bidirectional"))
    )
    (net (code "146") (name "unconnected-(U2-IM3-Pad21)") (class "Default")
      (node (ref "U2") (pin "21") (pinfunction "IM3_21") (pintype "bidirectional"))
    )
    (net (code "147") (name "unconnected-(U2-RES-Pad31)") (class "Default")
      (node (ref "U2") (pin "31") (pinfunction "RES_31") (pintype "bidirectional"))
    )
    (net (code "148") (name "unconnected-(U3-PadVIN)") (class "Default")
      (node (ref "U3") (pin "VIN") (pinfunction "VIN_VIN") (pintype "bidirectional"))
    )
  )
)
